# EEPROM_Temp_LEDs.net
KiCad netlist of a schematic drawn in Altium Designer
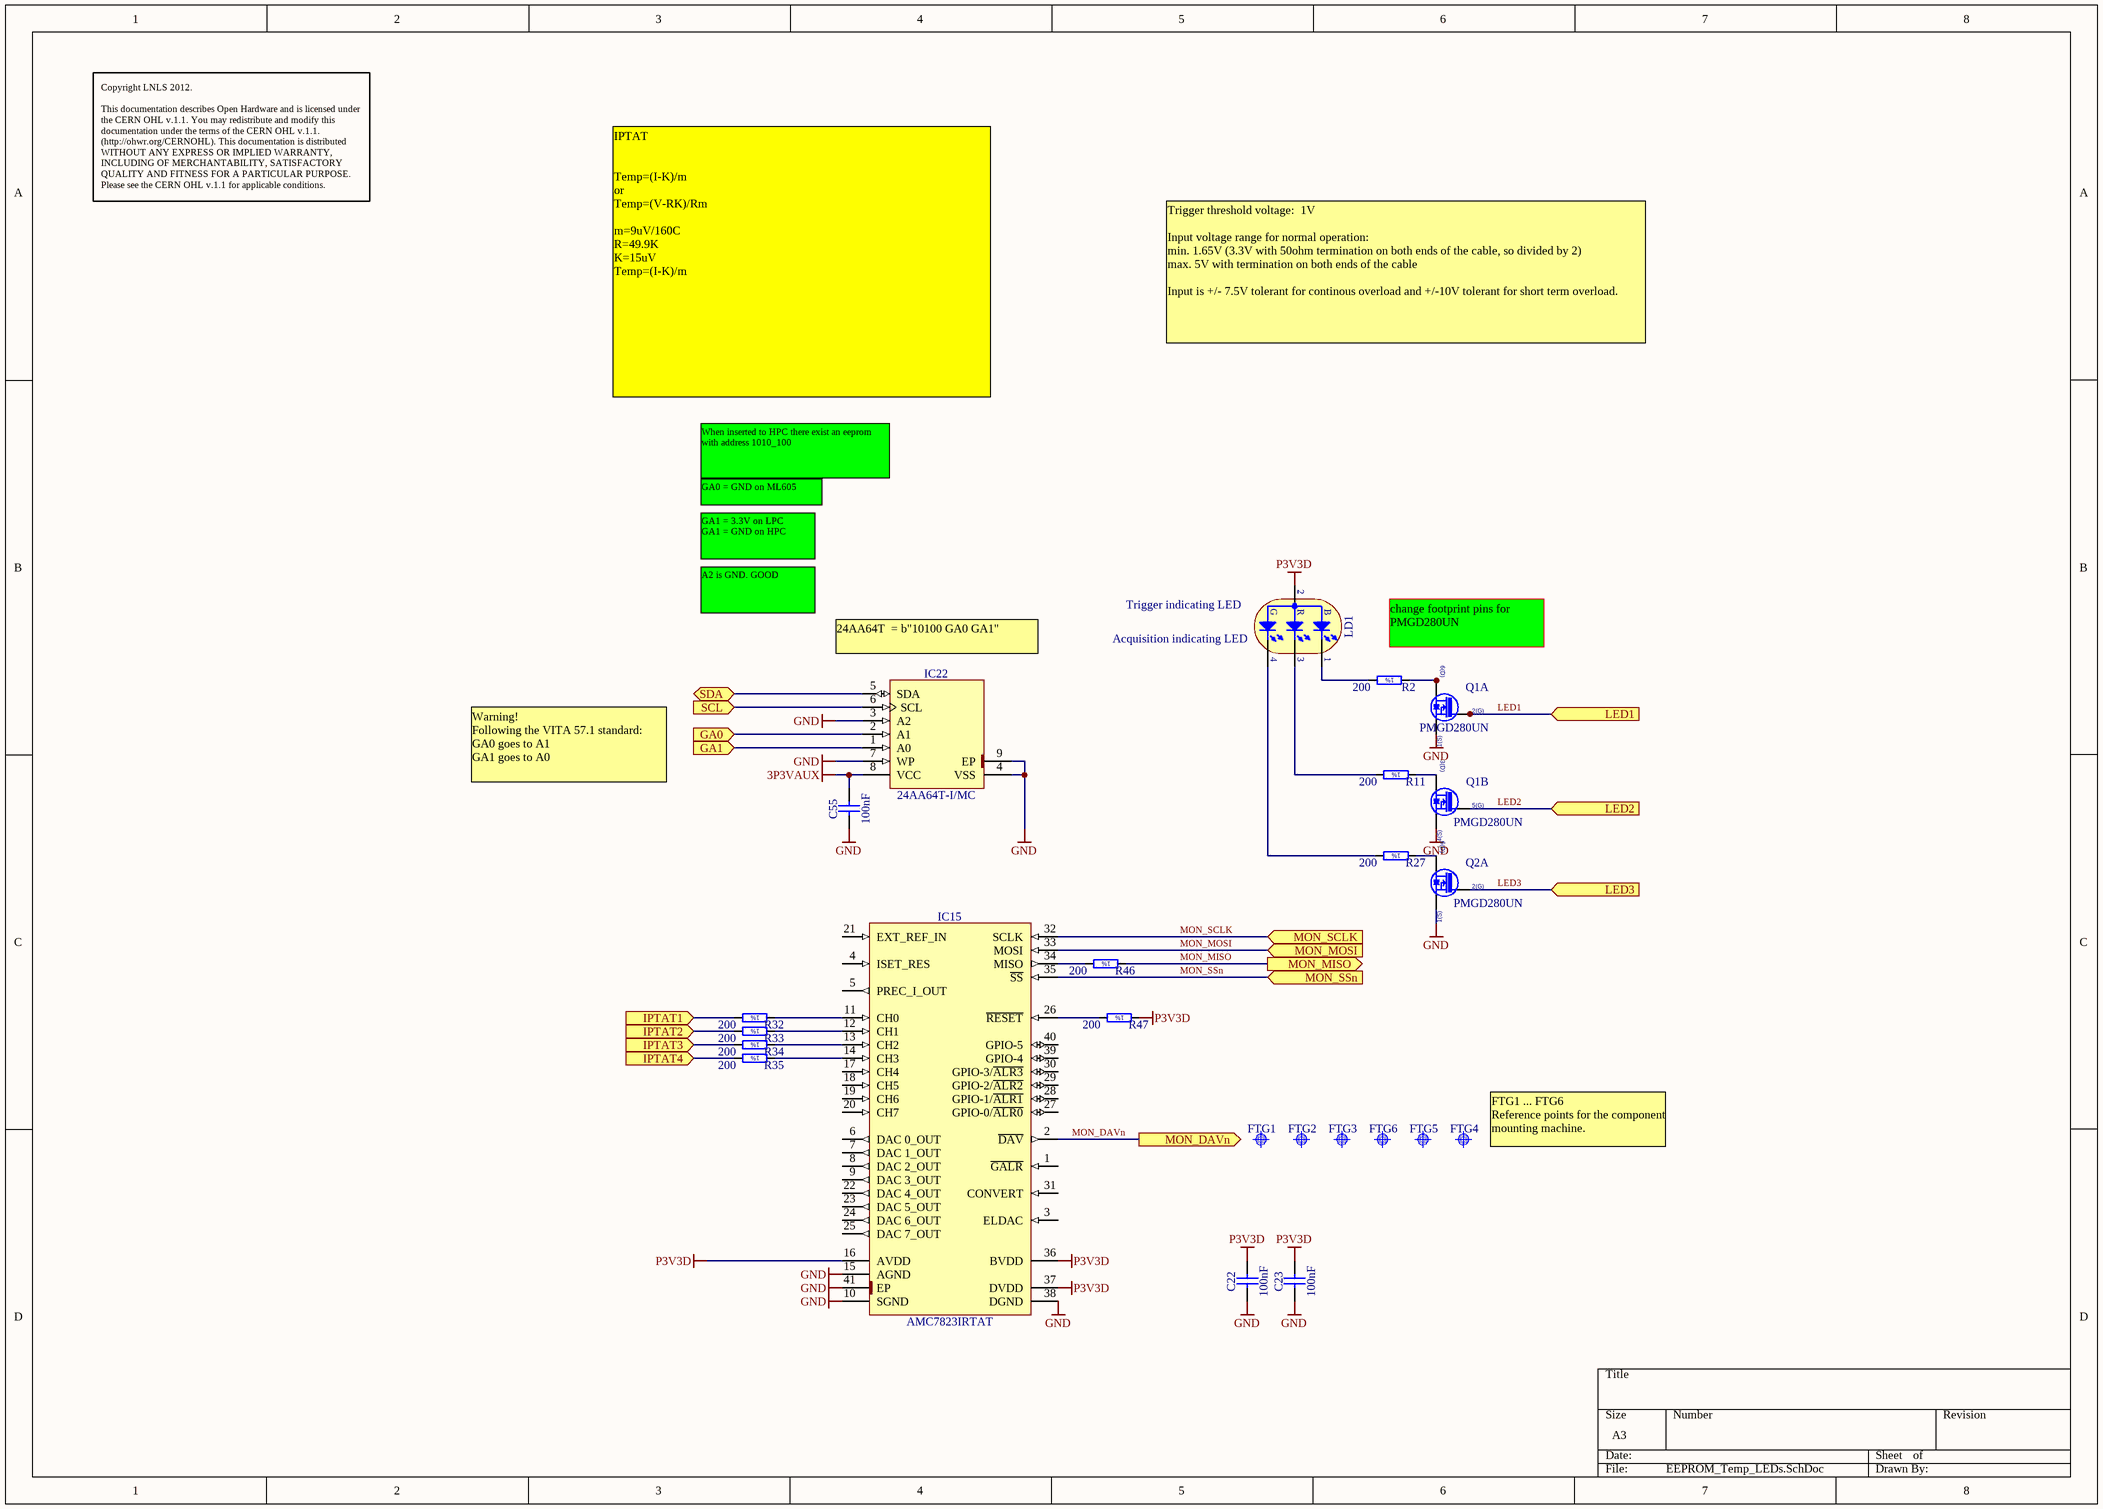
[diagram p0: EEPROM_Temp_LEDs.SchDoc]

(export (version "E")
  (design (tool "Eeschema 10.0.6"))
  (components
    (comp (ref "C22")
      (value "100nF")
      (footprint "CAPC0603X33N")
      (description "Non-polarised capacitor")
      (fields
        (field (name "PART NUMBER") "CC0201_100NF_6.3V_10%_X5R")
        (field (name "VOLTAGE") "6.3V")
        (field (name "AUTHOR") "CERN DEM JLC")
      )
      (libsource (lib "Capacitors") (part "Capacitor - non polarized"))
    )
    (comp (ref "C23")
      (value "100nF")
      (footprint "CAPC0603X33N")
      (description "Non-polarised capacitor")
      (fields
        (field (name "PART NUMBER") "CC0201_100NF_6.3V_10%_X5R")
        (field (name "VOLTAGE") "6.3V")
        (field (name "AUTHOR") "CERN DEM JLC")
      )
      (libsource (lib "Capacitors") (part "Capacitor - non polarized"))
    )
    (comp (ref "C55")
      (value "100nF")
      (footprint "CAPC0603X33N")
      (description "Non-polarised capacitor")
      (fields
        (field (name "PART NUMBER") "CC0201_100NF_6.3V_10%_X5R")
        (field (name "VOLTAGE") "6.3V")
        (field (name "AUTHOR") "CERN DEM JLC")
      )
      (libsource (lib "Capacitors") (part "Capacitor - non polarized"))
    )
    (comp (ref "FTG1")
      (value "Use only in PCB")
      (footprint "FIDUCIAL_TOP_S100-200")
      (description "Fiducial Target")
      (fields (field (name "PART NUMBER") "FIDUCIAL_TARGET_S100-200") (field (name "AUTHOR") "CERN DEM JLC"))
      (libsource (lib "Eletro-mechanical") (part "Fiducial Target"))
    )
    (comp (ref "FTG2")
      (value "Use only in PCB")
      (footprint "FIDUCIAL_TOP_S100-200")
      (description "Fiducial Target")
      (fields (field (name "PART NUMBER") "FIDUCIAL_TARGET_S100-200") (field (name "AUTHOR") "CERN DEM JLC"))
      (libsource (lib "Eletro-mechanical") (part "Fiducial Target"))
    )
    (comp (ref "FTG3")
      (value "Use only in PCB")
      (footprint "FIDUCIAL_TOP_S100-200")
      (description "Fiducial Target")
      (fields (field (name "PART NUMBER") "FIDUCIAL_TARGET_S100-200") (field (name "AUTHOR") "CERN DEM JLC"))
      (libsource (lib "Eletro-mechanical") (part "Fiducial Target"))
    )
    (comp (ref "FTG4")
      (value "Use only in PCB")
      (footprint "FIDUCIAL_TOP_S100-200")
      (description "Fiducial Target")
      (fields (field (name "PART NUMBER") "FIDUCIAL_TARGET_S100-200") (field (name "AUTHOR") "CERN DEM JLC"))
      (libsource (lib "Eletro-mechanical") (part "Fiducial Target"))
    )
    (comp (ref "FTG5")
      (value "Use only in PCB")
      (footprint "FIDUCIAL_TOP_S100-200")
      (description "Fiducial Target")
      (fields (field (name "PART NUMBER") "FIDUCIAL_TARGET_S100-200") (field (name "AUTHOR") "CERN DEM JLC"))
      (libsource (lib "Eletro-mechanical") (part "Fiducial Target"))
    )
    (comp (ref "FTG6")
      (value "Use only in PCB")
      (footprint "FIDUCIAL_TOP_S100-200")
      (description "Fiducial Target")
      (fields (field (name "PART NUMBER") "FIDUCIAL_TARGET_S100-200") (field (name "AUTHOR") "CERN DEM JLC"))
      (libsource (lib "Eletro-mechanical") (part "Fiducial Target"))
    )
    (comp (ref "IC15")
      (value "AMC7823IRTAT")
      (footprint "QFN50P600X600X80-41N-S425")
      (description "Integrated, Multichannel ADC and DAC for Analog Monitoring & Control")
      (fields (field (name "MANUFACTURER") "TEXAS INSTRUMENTS") (field (name "AUTHOR") "CERN DEM JLC"))
      (libsource (lib "ICs And Semiconductors") (part "AMC7823"))
    )
    (comp (ref "IC22")
      (value "24AA64T-I/MC")
      (footprint "SON50P300X200X100-9N-R175X155")
      (description "1.7-5.5V 64K I2C Serial EEPROM")
      (fields (field (name "MANUFACTURER") "MICROCHIP TECHNOLOGY") (field (name "AUTHOR") "CERN DEM JLC"))
      (libsource (lib "ICs And Semiconductors") (part "24AA64T-I/MC"))
    )
    (comp (ref "LD1")
      (value "~")
      (footprint "LED_AVAGO_HSMF-C113")
      (description "Tricolor LEDs 1 Cathode Blue, 2 Common Anode, 3 Cathode Red, 4 Cathode Green")
      (fields
        (field (name "PART NUMBER") "LED_AVAGO_HSMF-C113")
        (field (name "MANUFACTURER") "AVAGO TECHNOLOGIES")
        (field (name "AUTHOR") "CERN DEM JLC")
      )
      (libsource (lib "ICs And Semiconductors") (part "LED Blue-Red-Green 1CB_2AC_3CR_4CG"))
    )
    (comp (ref "Q1")
      (value "PMGD280UN")
      (footprint "SOT65P210X110-6N")
      (description "Dual N-Channel micro TrenchMOS™ Ultra Low Level FET")
      (fields (field (name "MANUFACTURER") "NXP SEMICONDUCTORS") (field (name "AUTHOR") "CERN DEM JLC"))
      (libsource (lib "ICs And Semiconductors") (part "PMGD280UN"))
    )
    (comp (ref "Q2")
      (value "PMGD280UN")
      (footprint "SOT65P210X110-6N")
      (description "Dual N-Channel micro TrenchMOS™ Ultra Low Level FET")
      (fields (field (name "MANUFACTURER") "NXP SEMICONDUCTORS") (field (name "AUTHOR") "CERN DEM JLC"))
      (libsource (lib "ICs And Semiconductors") (part "PMGD280UN"))
    )
    (comp (ref "R2")
      (value "200")
      (footprint "RESC1005X40N")
      (description "Resistor - 1%")
      (fields
        (field (name "PART NUMBER") "R0402_200R_1%_0.0625W_100PPM")
        (field (name "POWER") "0.0625W")
        (field (name "AUTHOR") "CERN DEM JLC")
      )
      (libsource (lib "Resistors") (part "Resistor - 1%"))
    )
    (comp (ref "R11")
      (value "200")
      (footprint "RESC1005X40N")
      (description "Resistor - 1%")
      (fields
        (field (name "PART NUMBER") "R0402_200R_1%_0.0625W_100PPM")
        (field (name "POWER") "0.0625W")
        (field (name "AUTHOR") "CERN DEM JLC")
      )
      (libsource (lib "Resistors") (part "Resistor - 1%"))
    )
    (comp (ref "R27")
      (value "200")
      (footprint "RESC1005X40N")
      (description "Resistor - 1%")
      (fields
        (field (name "PART NUMBER") "R0402_200R_1%_0.0625W_100PPM")
        (field (name "POWER") "0.0625W")
        (field (name "AUTHOR") "CERN DEM JLC")
      )
      (libsource (lib "Resistors") (part "Resistor - 1%"))
    )
    (comp (ref "R32")
      (value "200")
      (footprint "RESC1005X40N")
      (description "Resistor - 1%")
      (fields
        (field (name "PART NUMBER") "R0402_200R_1%_0.0625W_100PPM")
        (field (name "POWER") "0.0625W")
        (field (name "AUTHOR") "CERN DEM JLC")
      )
      (libsource (lib "Resistors") (part "Resistor - 1%"))
    )
    (comp (ref "R33")
      (value "200")
      (footprint "RESC1005X40N")
      (description "Resistor - 1%")
      (fields
        (field (name "PART NUMBER") "R0402_200R_1%_0.0625W_100PPM")
        (field (name "POWER") "0.0625W")
        (field (name "AUTHOR") "CERN DEM JLC")
      )
      (libsource (lib "Resistors") (part "Resistor - 1%"))
    )
    (comp (ref "R34")
      (value "200")
      (footprint "RESC1005X40N")
      (description "Resistor - 1%")
      (fields
        (field (name "PART NUMBER") "R0402_200R_1%_0.0625W_100PPM")
        (field (name "POWER") "0.0625W")
        (field (name "AUTHOR") "CERN DEM JLC")
      )
      (libsource (lib "Resistors") (part "Resistor - 1%"))
    )
    (comp (ref "R35")
      (value "200")
      (footprint "RESC1005X40N")
      (description "Resistor - 1%")
      (fields
        (field (name "PART NUMBER") "R0402_200R_1%_0.0625W_100PPM")
        (field (name "POWER") "0.0625W")
        (field (name "AUTHOR") "CERN DEM JLC")
      )
      (libsource (lib "Resistors") (part "Resistor - 1%"))
    )
    (comp (ref "R46")
      (value "200")
      (footprint "RESC1005X40N")
      (description "Resistor - 1%")
      (fields
        (field (name "PART NUMBER") "R0402_200R_1%_0.0625W_100PPM")
        (field (name "POWER") "0.0625W")
        (field (name "AUTHOR") "CERN DEM JLC")
      )
      (libsource (lib "Resistors") (part "Resistor - 1%"))
    )
    (comp (ref "R47")
      (value "200")
      (footprint "RESC1005X40N")
      (description "Resistor - 1%")
      (fields
        (field (name "PART NUMBER") "R0402_200R_1%_0.0625W_100PPM")
        (field (name "POWER") "0.0625W")
        (field (name "AUTHOR") "CERN DEM JLC")
      )
      (libsource (lib "Resistors") (part "Resistor - 1%"))
    )
  )
  (nets
    (net (code "1") (name "/GA0") (class "Default")
      (node (ref "IC22") (pin "2") (pinfunction "A1_2") (pintype "input"))
    )
    (net (code "2") (name "/GA1") (class "Default")
      (node (ref "IC22") (pin "1") (pinfunction "A0_1") (pintype "input"))
    )
    (net (code "3") (name "/IPTAT1") (class "Default")
      (node (ref "R32") (pin "2") (pinfunction "2_2") (pintype "passive"))
    )
    (net (code "4") (name "/IPTAT2") (class "Default")
      (node (ref "R33") (pin "2") (pinfunction "2_2") (pintype "passive"))
    )
    (net (code "5") (name "/IPTAT3") (class "Default")
      (node (ref "R34") (pin "2") (pinfunction "2_2") (pintype "passive"))
    )
    (net (code "6") (name "/IPTAT4") (class "Default")
      (node (ref "R35") (pin "2") (pinfunction "2_2") (pintype "passive"))
    )
    (net (code "7") (name "/LED1") (class "Default")
      (node (ref "Q1") (pin "2") (pinfunction "G_2") (pintype "passive"))
    )
    (net (code "8") (name "/LED2") (class "Default")
      (node (ref "Q1") (pin "5") (pinfunction "G_5") (pintype "passive"))
    )
    (net (code "9") (name "/LED3") (class "Default")
      (node (ref "Q2") (pin "2") (pinfunction "G_2") (pintype "passive"))
    )
    (net (code "10") (name "/MON_DAVn") (class "Default")
      (node (ref "IC15") (pin "2") (pinfunction "~{DAV}_2") (pintype "output"))
    )
    (net (code "11") (name "/MON_MISO") (class "Default")
      (node (ref "R46") (pin "1") (pinfunction "1_1") (pintype "passive"))
    )
    (net (code "12") (name "/MON_MOSI") (class "Default")
      (node (ref "IC15") (pin "33") (pinfunction "MOSI_33") (pintype "input"))
    )
    (net (code "13") (name "/MON_SCLK") (class "Default")
      (node (ref "IC15") (pin "32") (pinfunction "SCLK_32") (pintype "input"))
    )
    (net (code "14") (name "/MON_SSn") (class "Default")
      (node (ref "IC15") (pin "35") (pinfunction "~{SS}_35") (pintype "input"))
    )
    (net (code "15") (name "/SCL") (class "Default")
      (node (ref "IC22") (pin "6") (pinfunction "SCL_6") (pintype "input"))
    )
    (net (code "16") (name "/SDA") (class "Default")
      (node (ref "IC22") (pin "5") (pinfunction "SDA_5") (pintype "bidirectional"))
    )
    (net (code "17") (name "3P3VAUX") (class "Default")
      (node (ref "C55") (pin "2") (pinfunction "2_2") (pintype "passive"))
      (node (ref "IC22") (pin "8") (pinfunction "VCC_8") (pintype "power_in"))
    )
    (net (code "18") (name "GND") (class "Default")
      (node (ref "C22") (pin "1") (pinfunction "1_1") (pintype "passive"))
      (node (ref "C23") (pin "1") (pinfunction "1_1") (pintype "passive"))
      (node (ref "C55") (pin "1") (pinfunction "1_1") (pintype "passive"))
      (node (ref "IC15") (pin "10") (pinfunction "SGND_10") (pintype "power_in"))
      (node (ref "IC15") (pin "15") (pinfunction "AGND_15") (pintype "power_in"))
      (node (ref "IC15") (pin "38") (pinfunction "DGND_38") (pintype "power_in"))
      (node (ref "IC15") (pin "41") (pinfunction "EP_41") (pintype "power_in"))
      (node (ref "IC22") (pin "3") (pinfunction "A2_3") (pintype "input"))
      (node (ref "IC22") (pin "4") (pinfunction "VSS_4") (pintype "power_in"))
      (node (ref "IC22") (pin "7") (pinfunction "WP_7") (pintype "input"))
      (node (ref "IC22") (pin "9") (pinfunction "EP_9") (pintype "power_in"))
      (node (ref "Q1") (pin "1") (pinfunction "S_1") (pintype "passive"))
      (node (ref "Q1") (pin "4") (pinfunction "S_4") (pintype "passive"))
      (node (ref "Q2") (pin "1") (pinfunction "S_1") (pintype "passive"))
    )
    (net (code "19") (name "Net-(IC15-CH0)") (class "Default")
      (node (ref "IC15") (pin "11") (pinfunction "CH0_11") (pintype "input"))
      (node (ref "R32") (pin "1") (pinfunction "1_1") (pintype "passive"))
    )
    (net (code "20") (name "Net-(IC15-CH1)") (class "Default")
      (node (ref "IC15") (pin "12") (pinfunction "CH1_12") (pintype "input"))
      (node (ref "R33") (pin "1") (pinfunction "1_1") (pintype "passive"))
    )
    (net (code "21") (name "Net-(IC15-CH2)") (class "Default")
      (node (ref "IC15") (pin "13") (pinfunction "CH2_13") (pintype "input"))
      (node (ref "R34") (pin "1") (pinfunction "1_1") (pintype "passive"))
    )
    (net (code "22") (name "Net-(IC15-CH3)") (class "Default")
      (node (ref "IC15") (pin "14") (pinfunction "CH3_14") (pintype "input"))
      (node (ref "R35") (pin "1") (pinfunction "1_1") (pintype "passive"))
    )
    (net (code "23") (name "Net-(IC15-MISO)") (class "Default")
      (node (ref "IC15") (pin "34") (pinfunction "MISO_34") (pintype "output"))
      (node (ref "R46") (pin "2") (pinfunction "2_2") (pintype "passive"))
    )
    (net (code "24") (name "Net-(IC15-~{RESET})") (class "Default")
      (node (ref "IC15") (pin "26") (pinfunction "~{RESET}_26") (pintype "input"))
      (node (ref "R47") (pin "2") (pinfunction "2_2") (pintype "passive"))
    )
    (net (code "25") (name "Net-(LD1-CB)") (class "Default")
      (node (ref "LD1") (pin "1") (pinfunction "CB_1") (pintype "passive"))
      (node (ref "R2") (pin "2") (pinfunction "2_2") (pintype "passive"))
    )
    (net (code "26") (name "Net-(LD1-CG)") (class "Default")
      (node (ref "LD1") (pin "4") (pinfunction "CG_4") (pintype "passive"))
      (node (ref "R27") (pin "2") (pinfunction "2_2") (pintype "passive"))
    )
    (net (code "27") (name "Net-(LD1-CR)") (class "Default")
      (node (ref "LD1") (pin "3") (pinfunction "CR_3") (pintype "passive"))
      (node (ref "R11") (pin "2") (pinfunction "2_2") (pintype "passive"))
    )
    (net (code "28") (name "Net-(Q1A-D)") (class "Default")
      (node (ref "Q1") (pin "6") (pinfunction "D_6") (pintype "passive"))
      (node (ref "R2") (pin "1") (pinfunction "1_1") (pintype "passive"))
    )
    (net (code "29") (name "Net-(Q1B-D)") (class "Default")
      (node (ref "Q1") (pin "3") (pinfunction "D_3") (pintype "passive"))
      (node (ref "R11") (pin "1") (pinfunction "1_1") (pintype "passive"))
    )
    (net (code "30") (name "Net-(Q2A-D)") (class "Default")
      (node (ref "Q2") (pin "6") (pinfunction "D_6") (pintype "passive"))
      (node (ref "R27") (pin "1") (pinfunction "1_1") (pintype "passive"))
    )
    (net (code "31") (name "P3V3D") (class "Default")
      (node (ref "C22") (pin "2") (pinfunction "2_2") (pintype "passive"))
      (node (ref "C23") (pin "2") (pinfunction "2_2") (pintype "passive"))
      (node (ref "IC15") (pin "16") (pinfunction "AVDD_16") (pintype "power_in"))
      (node (ref "IC15") (pin "36") (pinfunction "BVDD_36") (pintype "power_in"))
      (node (ref "IC15") (pin "37") (pinfunction "DVDD_37") (pintype "power_in"))
      (node (ref "LD1") (pin "2") (pinfunction "AC_2") (pintype "passive"))
      (node (ref "R47") (pin "1") (pinfunction "1_1") (pintype "passive"))
    )
    (net (code "32") (name "unconnected-(IC15-CH4-Pad17)") (class "Default")
      (node (ref "IC15") (pin "17") (pinfunction "CH4_17") (pintype "input"))
    )
    (net (code "33") (name "unconnected-(IC15-CH5-Pad18)") (class "Default")
      (node (ref "IC15") (pin "18") (pinfunction "CH5_18") (pintype "input"))
    )
    (net (code "34") (name "unconnected-(IC15-CH6-Pad19)") (class "Default")
      (node (ref "IC15") (pin "19") (pinfunction "CH6_19") (pintype "input"))
    )
    (net (code "35") (name "unconnected-(IC15-CH7-Pad20)") (class "Default")
      (node (ref "IC15") (pin "20") (pinfunction "CH7_20") (pintype "input"))
    )
    (net (code "36") (name "unconnected-(IC15-CONVERT-Pad31)") (class "Default")
      (node (ref "IC15") (pin "31") (pinfunction "CONVERT_31") (pintype "input"))
    )
    (net (code "37") (name "unconnected-(IC15-DAC_0_OUT-Pad6)") (class "Default")
      (node (ref "IC15") (pin "6") (pinfunction "DAC_0_OUT_6") (pintype "output"))
    )
    (net (code "38") (name "unconnected-(IC15-DAC_1_OUT-Pad7)") (class "Default")
      (node (ref "IC15") (pin "7") (pinfunction "DAC_1_OUT_7") (pintype "output"))
    )
    (net (code "39") (name "unconnected-(IC15-DAC_2_OUT-Pad8)") (class "Default")
      (node (ref "IC15") (pin "8") (pinfunction "DAC_2_OUT_8") (pintype "output"))
    )
    (net (code "40") (name "unconnected-(IC15-DAC_3_OUT-Pad9)") (class "Default")
      (node (ref "IC15") (pin "9") (pinfunction "DAC_3_OUT_9") (pintype "output"))
    )
    (net (code "41") (name "unconnected-(IC15-DAC_4_OUT-Pad22)") (class "Default")
      (node (ref "IC15") (pin "22") (pinfunction "DAC_4_OUT_22") (pintype "output"))
    )
    (net (code "42") (name "unconnected-(IC15-DAC_5_OUT-Pad23)") (class "Default")
      (node (ref "IC15") (pin "23") (pinfunction "DAC_5_OUT_23") (pintype "output"))
    )
    (net (code "43") (name "unconnected-(IC15-DAC_6_OUT-Pad24)") (class "Default")
      (node (ref "IC15") (pin "24") (pinfunction "DAC_6_OUT_24") (pintype "output"))
    )
    (net (code "44") (name "unconnected-(IC15-DAC_7_OUT-Pad25)") (class "Default")
      (node (ref "IC15") (pin "25") (pinfunction "DAC_7_OUT_25") (pintype "output"))
    )
    (net (code "45") (name "unconnected-(IC15-ELDAC-Pad3)") (class "Default")
      (node (ref "IC15") (pin "3") (pinfunction "ELDAC_3") (pintype "input"))
    )
    (net (code "46") (name "unconnected-(IC15-EXT_REF_IN-Pad21)") (class "Default")
      (node (ref "IC15") (pin "21") (pinfunction "EXT_REF_IN_21") (pintype "input"))
    )
    (net (code "47") (name "unconnected-(IC15-GPIO-0{slash}~{ALR0}-Pad27)") (class "Default")
      (node (ref "IC15") (pin "27") (pinfunction "GPIO-0/~{ALR0}_27") (pintype "bidirectional"))
    )
    (net (code "48") (name "unconnected-(IC15-GPIO-1{slash}~{ALR1}-Pad28)") (class "Default")
      (node (ref "IC15") (pin "28") (pinfunction "GPIO-1/~{ALR1}_28") (pintype "bidirectional"))
    )
    (net (code "49") (name "unconnected-(IC15-GPIO-2{slash}~{ALR2}-Pad29)") (class "Default")
      (node (ref "IC15") (pin "29") (pinfunction "GPIO-2/~{ALR2}_29") (pintype "bidirectional"))
    )
    (net (code "50") (name "unconnected-(IC15-GPIO-3{slash}~{ALR3}-Pad30)") (class "Default")
      (node (ref "IC15") (pin "30") (pinfunction "GPIO-3/~{ALR3}_30") (pintype "bidirectional"))
    )
    (net (code "51") (name "unconnected-(IC15-GPIO-4-Pad39)") (class "Default")
      (node (ref "IC15") (pin "39") (pinfunction "GPIO-4_39") (pintype "bidirectional"))
    )
    (net (code "52") (name "unconnected-(IC15-GPIO-5-Pad40)") (class "Default")
      (node (ref "IC15") (pin "40") (pinfunction "GPIO-5_40") (pintype "bidirectional"))
    )
    (net (code "53") (name "unconnected-(IC15-ISET_RES-Pad4)") (class "Default")
      (node (ref "IC15") (pin "4") (pinfunction "ISET_RES_4") (pintype "input"))
    )
    (net (code "54") (name "unconnected-(IC15-PREC_I_OUT-Pad5)") (class "Default")
      (node (ref "IC15") (pin "5") (pinfunction "PREC_I_OUT_5") (pintype "output"))
    )
    (net (code "55") (name "unconnected-(IC15-~{GALR}-Pad1)") (class "Default")
      (node (ref "IC15") (pin "1") (pinfunction "~{GALR}_1") (pintype "input"))
    )
  )
)
